# piccolo_pcb_v0_9_1.net
KiCad netlist of a schematic drawn in EAGLE
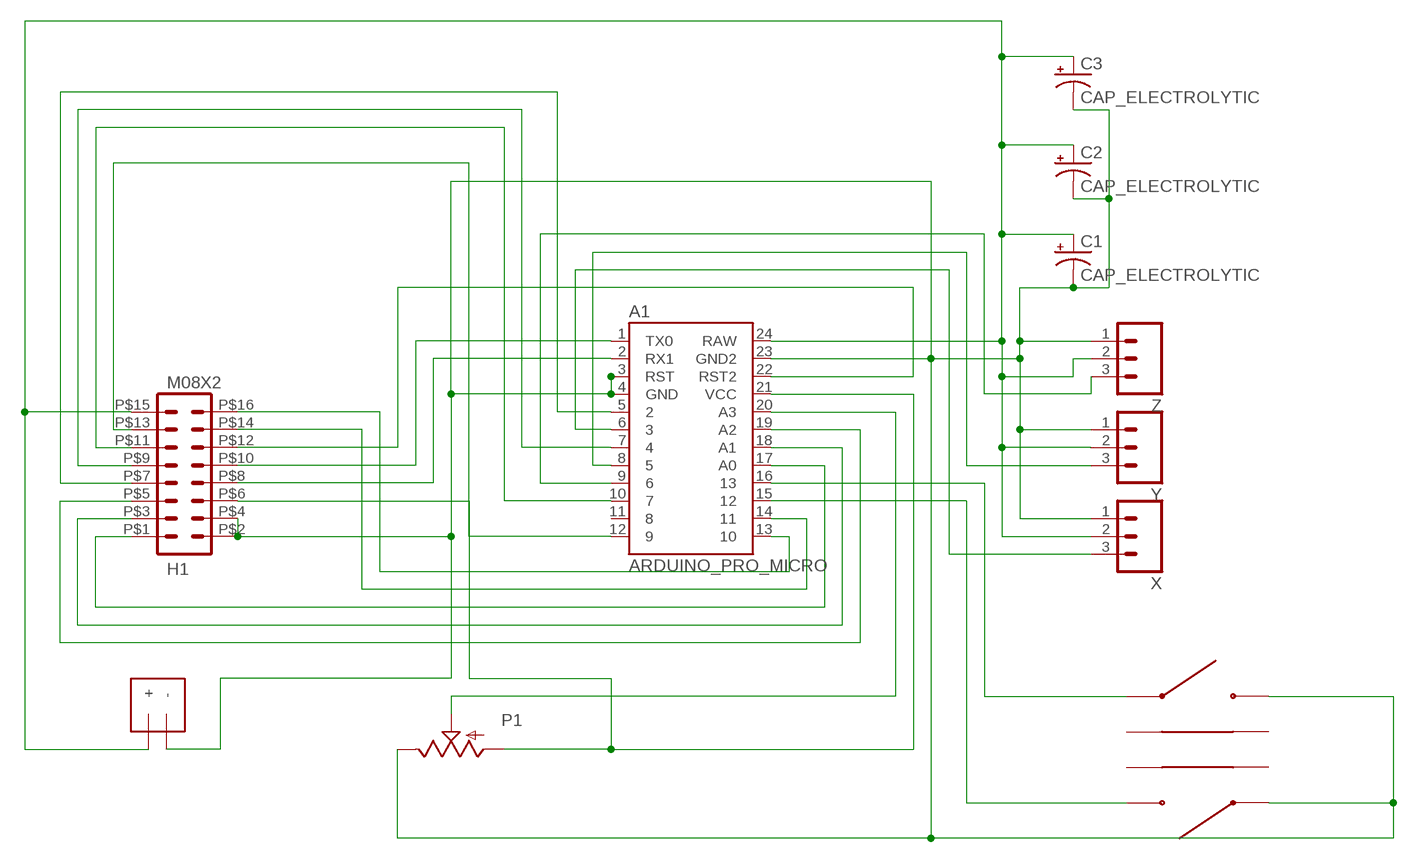
[diagram p0: schematic, sheet 1]

(export (version "E")
  (design (tool "Eeschema 10.0.6"))
  (components
    (comp (ref "A1")
      (value "ARDUINO_PRO_MICRO")
      (footprint "eagle-import:ARDUINO_MINI")
      (libsource (lib "eagle-import") (part "ARDUINO_MINI"))
    )
    (comp (ref "C1")
      (value "CAP_ELECTROLYTIC")
      (footprint "eagle-import:RADIAL_330UF")
      (libsource (lib "eagle-import") (part "CAP_ELECTROLYTIC"))
    )
    (comp (ref "C2")
      (value "CAP_ELECTROLYTIC")
      (footprint "eagle-import:RADIAL_330UF")
      (libsource (lib "eagle-import") (part "CAP_ELECTROLYTIC"))
    )
    (comp (ref "C3")
      (value "CAP_ELECTROLYTIC")
      (footprint "eagle-import:RADIAL_330UF")
      (libsource (lib "eagle-import") (part "CAP_ELECTROLYTIC"))
    )
    (comp (ref "DC_IN")
      (value "4.8v-6.0v")
      (footprint "eagle-import:JST-PH-2-PTH")
      (libsource (lib "eagle-import") (part "M02-POL"))
    )
    (comp (ref "H1")
      (value "M08X2")
      (footprint "eagle-import:PTH_2X8_90DEG_FEMALE")
      (libsource (lib "eagle-import") (part "M08X2"))
    )
    (comp (ref "P1")
      (value "POTTHUMBWHEEL")
      (footprint "eagle-import:16MM_THUMBWHEEL")
      (libsource (lib "eagle-import") (part "POTTHUMBWHEEL"))
    )
    (comp (ref "S1")
      (value "SWITCH_TACTILE")
      (footprint "eagle-import:RIGHT_ANGLE_TACTSWITCH")
      (libsource (lib "eagle-import") (part "SWITCH_TACTILE"))
    )
    (comp (ref "S2")
      (value "SWITCH_TACTILE")
      (footprint "eagle-import:RIGHT_ANGLE_TACTSWITCH")
      (libsource (lib "eagle-import") (part "SWITCH_TACTILE"))
    )
    (comp (ref "X")
      (value "M03PTH")
      (footprint "eagle-import:1X03")
      (libsource (lib "eagle-import") (part "M03PTH"))
    )
    (comp (ref "Y")
      (value "M03PTH")
      (footprint "eagle-import:1X03")
      (libsource (lib "eagle-import") (part "M03PTH"))
    )
    (comp (ref "Z")
      (value "M03PTH")
      (footprint "eagle-import:1X03")
      (libsource (lib "eagle-import") (part "M03PTH"))
    )
  )
  (nets
    (net (code "1") (name "Net-(A1-2)") (class "Default")
      (node (ref "A1") (pin "5") (pinfunction "2_5") (pintype "bidirectional"))
      (node (ref "H1") (pin "P$7") (pinfunction "7_P$7") (pintype "passive"))
    )
    (net (code "2") (name "Net-(A1-3)") (class "Default")
      (node (ref "A1") (pin "6") (pinfunction "3_6") (pintype "bidirectional"))
      (node (ref "X") (pin "3") (pinfunction "3_3") (pintype "passive"))
    )
    (net (code "3") (name "Net-(A1-4)") (class "Default")
      (node (ref "A1") (pin "7") (pinfunction "4_7") (pintype "bidirectional"))
      (node (ref "H1") (pin "P$9") (pinfunction "9_P$9") (pintype "passive"))
    )
    (net (code "4") (name "Net-(A1-5)") (class "Default")
      (node (ref "A1") (pin "8") (pinfunction "5_8") (pintype "bidirectional"))
      (node (ref "Y") (pin "3") (pinfunction "3_3") (pintype "passive"))
    )
    (net (code "5") (name "Net-(A1-6)") (class "Default")
      (node (ref "A1") (pin "9") (pinfunction "6_9") (pintype "bidirectional"))
      (node (ref "Z") (pin "3") (pinfunction "3_3") (pintype "passive"))
    )
    (net (code "6") (name "Net-(A1-7)") (class "Default")
      (node (ref "A1") (pin "10") (pinfunction "7_10") (pintype "bidirectional"))
      (node (ref "H1") (pin "P$11") (pinfunction "11_P$11") (pintype "passive"))
    )
    (net (code "7") (name "Net-(A1-9)") (class "Default")
      (node (ref "A1") (pin "12") (pinfunction "9_12") (pintype "bidirectional"))
      (node (ref "H1") (pin "P$13") (pinfunction "13_P$13") (pintype "passive"))
    )
    (net (code "8") (name "Net-(A1-10)") (class "Default")
      (node (ref "A1") (pin "13") (pinfunction "10_13") (pintype "bidirectional"))
      (node (ref "H1") (pin "P$16") (pinfunction "16_P$16") (pintype "passive"))
    )
    (net (code "9") (name "Net-(A1-11)") (class "Default")
      (node (ref "A1") (pin "14") (pinfunction "11_14") (pintype "bidirectional"))
      (node (ref "H1") (pin "P$14") (pinfunction "14_P$14") (pintype "passive"))
    )
    (net (code "10") (name "Net-(A1-12)") (class "Default")
      (node (ref "A1") (pin "15") (pinfunction "12_15") (pintype "bidirectional"))
      (node (ref "S1") (pin "2") (pinfunction "2_2") (pintype "bidirectional"))
    )
    (net (code "11") (name "Net-(A1-13)") (class "Default")
      (node (ref "A1") (pin "16") (pinfunction "13_16") (pintype "bidirectional"))
      (node (ref "S2") (pin "1") (pinfunction "1_1") (pintype "bidirectional"))
    )
    (net (code "12") (name "Net-(A1-A0)") (class "Default")
      (node (ref "A1") (pin "17") (pinfunction "A0_17") (pintype "bidirectional"))
      (node (ref "H1") (pin "P$1") (pinfunction "1_P$1") (pintype "passive"))
    )
    (net (code "13") (name "Net-(A1-A1)") (class "Default")
      (node (ref "A1") (pin "18") (pinfunction "A1_18") (pintype "bidirectional"))
      (node (ref "H1") (pin "P$3") (pinfunction "3_P$3") (pintype "passive"))
    )
    (net (code "14") (name "Net-(A1-A2)") (class "Default")
      (node (ref "A1") (pin "19") (pinfunction "A2_19") (pintype "bidirectional"))
      (node (ref "H1") (pin "P$5") (pinfunction "5_P$5") (pintype "passive"))
    )
    (net (code "15") (name "Net-(A1-A3)") (class "Default")
      (node (ref "A1") (pin "20") (pinfunction "A3_20") (pintype "bidirectional"))
      (node (ref "P1") (pin "P$2") (pinfunction "S_P$2") (pintype "passive"))
    )
    (net (code "16") (name "Net-(A1-GND)") (class "Default")
      (node (ref "A1") (pin "23") (pinfunction "GND2_23") (pintype "bidirectional"))
      (node (ref "A1") (pin "3") (pinfunction "RST_3") (pintype "bidirectional"))
      (node (ref "A1") (pin "4") (pinfunction "GND_4") (pintype "bidirectional"))
      (node (ref "C1") (pin "C") (pinfunction "-_C") (pintype "passive"))
      (node (ref "C2") (pin "C") (pinfunction "-_C") (pintype "passive"))
      (node (ref "C3") (pin "C") (pinfunction "-_C") (pintype "passive"))
      (node (ref "DC_IN") (pin "-") (pinfunction "-_-") (pintype "bidirectional"))
      (node (ref "H1") (pin "P$2") (pinfunction "2_P$2") (pintype "passive"))
      (node (ref "H1") (pin "P$4") (pinfunction "4_P$4") (pintype "passive"))
      (node (ref "P1") (pin "P$1") (pinfunction "E_P$1") (pintype "passive"))
      (node (ref "S1") (pin "1") (pinfunction "1_1") (pintype "bidirectional"))
      (node (ref "S2") (pin "2") (pinfunction "2_2") (pintype "bidirectional"))
      (node (ref "X") (pin "1") (pinfunction "1_1") (pintype "passive"))
      (node (ref "Y") (pin "1") (pinfunction "1_1") (pintype "passive"))
      (node (ref "Z") (pin "1") (pinfunction "1_1") (pintype "passive"))
    )
    (net (code "17") (name "Net-(A1-RAW)") (class "Default")
      (node (ref "A1") (pin "24") (pinfunction "RAW_24") (pintype "bidirectional"))
      (node (ref "C1") (pin "A") (pinfunction "+_A") (pintype "passive"))
      (node (ref "C2") (pin "A") (pinfunction "+_A") (pintype "passive"))
      (node (ref "C3") (pin "A") (pinfunction "+_A") (pintype "passive"))
      (node (ref "DC_IN") (pin "+") (pinfunction "+_+") (pintype "bidirectional"))
      (node (ref "H1") (pin "P$15") (pinfunction "15_P$15") (pintype "passive"))
      (node (ref "X") (pin "2") (pinfunction "2_2") (pintype "passive"))
      (node (ref "Y") (pin "2") (pinfunction "2_2") (pintype "passive"))
      (node (ref "Z") (pin "2") (pinfunction "2_2") (pintype "passive"))
    )
    (net (code "18") (name "Net-(A1-RST2)") (class "Default")
      (node (ref "A1") (pin "22") (pinfunction "RST2_22") (pintype "bidirectional"))
      (node (ref "H1") (pin "P$12") (pinfunction "12_P$12") (pintype "passive"))
    )
    (net (code "19") (name "Net-(A1-RX1)") (class "Default")
      (node (ref "A1") (pin "2") (pinfunction "RX1_2") (pintype "bidirectional"))
      (node (ref "H1") (pin "P$8") (pinfunction "8_P$8") (pintype "passive"))
    )
    (net (code "20") (name "Net-(A1-TX0)") (class "Default")
      (node (ref "A1") (pin "1") (pinfunction "TX0_1") (pintype "bidirectional"))
      (node (ref "H1") (pin "P$10") (pinfunction "10_P$10") (pintype "passive"))
    )
    (net (code "21") (name "Net-(A1-VCC)") (class "Default")
      (node (ref "A1") (pin "21") (pinfunction "VCC_21") (pintype "bidirectional"))
      (node (ref "H1") (pin "P$6") (pinfunction "6_P$6") (pintype "passive"))
      (node (ref "P1") (pin "P$3") (pinfunction "A_P$3") (pintype "passive"))
    )
    (net (code "22") (name "unconnected-(A1-8-Pad11)") (class "Default")
      (node (ref "A1") (pin "11") (pinfunction "8_11") (pintype "bidirectional"))
    )
    (net (code "23") (name "unconnected-(S1-GND1-PadPE1)") (class "Default")
      (node (ref "S1") (pin "PE1") (pinfunction "GND1_PE1") (pintype "bidirectional"))
    )
    (net (code "24") (name "unconnected-(S1-GND2-PadPE2)") (class "Default")
      (node (ref "S1") (pin "PE2") (pinfunction "GND2_PE2") (pintype "bidirectional"))
    )
    (net (code "25") (name "unconnected-(S2-GND1-PadPE1)") (class "Default")
      (node (ref "S2") (pin "PE1") (pinfunction "GND1_PE1") (pintype "bidirectional"))
    )
    (net (code "26") (name "unconnected-(S2-GND2-PadPE2)") (class "Default")
      (node (ref "S2") (pin "PE2") (pinfunction "GND2_PE2") (pintype "bidirectional"))
    )
  )
)
